# CHARGER_BOARD.net
KiCad netlist of a schematic drawn in Altium Designer
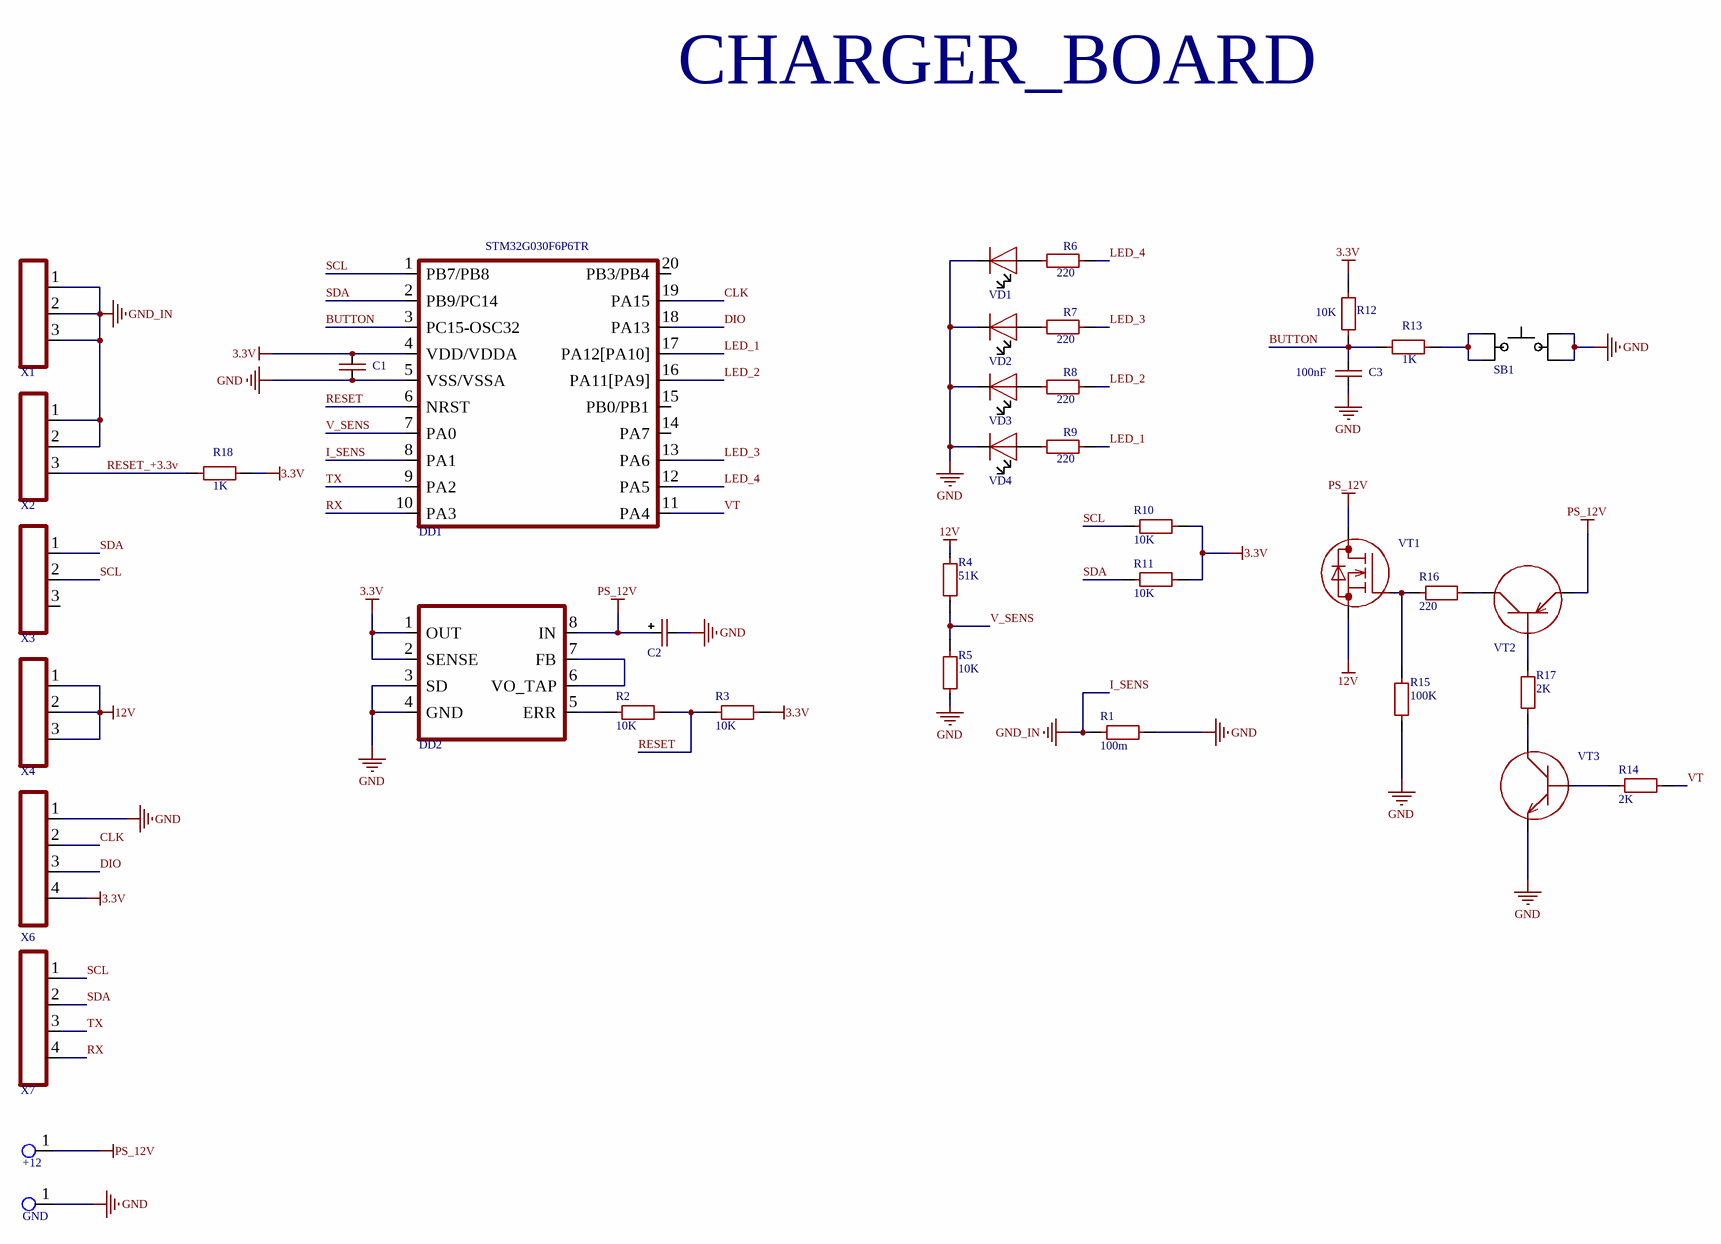
[diagram p0: CHARGER_BOARD.SchDoc]

(export (version "E")
  (design (tool "Eeschema 10.0.6"))
  (components
    (comp (ref "+12") (value "Test_Point_PCB") (footprint "Point") (libsource (lib "POINT") (part "POINT")))
    (comp (ref "C1")
      (value "CAP-NON-POLAR")
      (footprint "CAP-0603")
      (libsource (lib "PASSIVE_COMPONENTS") (part "CAP-NON-POLAR"))
    )
    (comp (ref "C2")
      (value "CAP-POLAR")
      (footprint "CAP-TAN-C")
      (libsource (lib "PASSIVE_COMPONENTS") (part "CAP-POLAR"))
    )
    (comp (ref "C3")
      (value "100nF")
      (footprint "CAP-0603")
      (libsource (lib "PASSIVE_COMPONENTS") (part "CAP-NON-POLAR"))
    )
    (comp (ref "DD1")
      (value "STM32G030F6P6TR")
      (footprint "TSSOP-20")
      (libsource (lib "STM32G030F6P6TR") (part "STM32G030F6P6TR"))
    )
    (comp (ref "DD2") (value "LP2951") (footprint "SO8-150") (libsource (lib "LP2951") (part "LP2951")))
    (comp (ref "GND") (value "Test_Point_PCB") (footprint "Point") (libsource (lib "POINT") (part "POINT")))
    (comp (ref "R1")
      (value "100m")
      (footprint "RES-2512")
      (libsource (lib "PASSIVE_COMPONENTS") (part "RES-CONST"))
    )
    (comp (ref "R2")
      (value "10K")
      (footprint "RES-0603")
      (libsource (lib "PASSIVE_COMPONENTS") (part "RES-CONST"))
    )
    (comp (ref "R3")
      (value "10K")
      (footprint "RES-0603")
      (libsource (lib "PASSIVE_COMPONENTS") (part "RES-CONST"))
    )
    (comp (ref "R4")
      (value "51K")
      (footprint "RES-0603")
      (libsource (lib "PASSIVE_COMPONENTS") (part "RES-CONST"))
    )
    (comp (ref "R5")
      (value "10K")
      (footprint "RES-0603")
      (libsource (lib "PASSIVE_COMPONENTS") (part "RES-CONST"))
    )
    (comp (ref "R6")
      (value "220")
      (footprint "RES-0603")
      (libsource (lib "PASSIVE_COMPONENTS") (part "RES-CONST"))
    )
    (comp (ref "R7")
      (value "220")
      (footprint "RES-0603")
      (libsource (lib "PASSIVE_COMPONENTS") (part "RES-CONST"))
    )
    (comp (ref "R8")
      (value "220")
      (footprint "RES-0603")
      (libsource (lib "PASSIVE_COMPONENTS") (part "RES-CONST"))
    )
    (comp (ref "R9")
      (value "220")
      (footprint "RES-0603")
      (libsource (lib "PASSIVE_COMPONENTS") (part "RES-CONST"))
    )
    (comp (ref "R10")
      (value "10K")
      (footprint "RES-0603")
      (libsource (lib "PASSIVE_COMPONENTS") (part "RES-CONST"))
    )
    (comp (ref "R11")
      (value "10K")
      (footprint "RES-0603")
      (libsource (lib "PASSIVE_COMPONENTS") (part "RES-CONST"))
    )
    (comp (ref "R12")
      (value "10K")
      (footprint "RES-0603")
      (libsource (lib "PASSIVE_COMPONENTS") (part "RES-CONST"))
    )
    (comp (ref "R13")
      (value "1K")
      (footprint "RES-0603")
      (libsource (lib "PASSIVE_COMPONENTS") (part "RES-CONST"))
    )
    (comp (ref "R14")
      (value "2K")
      (footprint "RES-0603")
      (libsource (lib "PASSIVE_COMPONENTS") (part "RES-CONST"))
    )
    (comp (ref "R15")
      (value "100K")
      (footprint "RES-0603")
      (libsource (lib "PASSIVE_COMPONENTS") (part "RES-CONST"))
    )
    (comp (ref "R16")
      (value "220")
      (footprint "RES-0603")
      (libsource (lib "PASSIVE_COMPONENTS") (part "RES-CONST"))
    )
    (comp (ref "R17")
      (value "2K")
      (footprint "RES-0603")
      (libsource (lib "PASSIVE_COMPONENTS") (part "RES-CONST"))
    )
    (comp (ref "R18")
      (value "1K")
      (footprint "RES-0603")
      (libsource (lib "PASSIVE_COMPONENTS") (part "RES-CONST"))
    )
    (comp (ref "SB1")
      (value "BUTTON-TACT-4PIN")
      (footprint "TACTB-6x6 SMD")
      (libsource (lib "TACTB-6x6 SMD") (part "BUTTON-TACT-4PIN"))
    )
    (comp (ref "VD1") (value "LED") (footprint "LED-0603") (libsource (lib "LED") (part "LED")))
    (comp (ref "VD2") (value "LED") (footprint "LED-0603") (libsource (lib "LED") (part "LED")))
    (comp (ref "VD3") (value "LED") (footprint "LED-0603") (libsource (lib "LED") (part "LED")))
    (comp (ref "VD4") (value "LED") (footprint "LED-0603") (libsource (lib "LED") (part "LED")))
    (comp (ref "VT1")
      (value "MOSFET-N-GDS")
      (footprint "TO252")
      (libsource (lib "AOD514") (part "MOSFET-N-GDS"))
    )
    (comp (ref "VT2") (value "BC857-BEC") (footprint "SOT23-3") (libsource (lib "BC8XX") (part "BC857-BEC")))
    (comp (ref "VT3") (value "BC847-BEC") (footprint "SOT23-3") (libsource (lib "BC8XX") (part "BC847-BEC")))
    (comp (ref "X1")
      (value "CONN-3-PIN")
      (footprint "4-SMD")
      (libsource (lib "Spring Compression Contact 2.5 mm") (part "CONN-3-PIN"))
    )
    (comp (ref "X2")
      (value "CONN-3-PIN")
      (footprint "4-SMD")
      (libsource (lib "Spring Compression Contact 2.5 mm") (part "CONN-3-PIN"))
    )
    (comp (ref "X3")
      (value "CONN-3-PIN")
      (footprint "4-SMD")
      (libsource (lib "Spring Compression Contact 2.5 mm") (part "CONN-3-PIN"))
    )
    (comp (ref "X4")
      (value "CONN-3-PIN")
      (footprint "4-SMD")
      (libsource (lib "Spring Compression Contact 2.5 mm") (part "CONN-3-PIN"))
    )
    (comp (ref "X6")
      (value "CONN-4-PIN")
      (footprint "CONN-PLS-4-2.54mm")
      (libsource (lib "CONNECTORS") (part "CONN-4-PIN"))
    )
    (comp (ref "X7")
      (value "CONN-4-PIN")
      (footprint "CONN-PLS-4-2.54mm")
      (libsource (lib "CONNECTORS") (part "CONN-4-PIN"))
    )
  )
  (nets
    (net (code "1") (name "/BUTTON") (class "Default")
      (node (ref "C3") (pin "2") (pinfunction "2_2") (pintype "passive"))
      (node (ref "DD1") (pin "3") (pinfunction "PC15-OSC32_3") (pintype "passive"))
      (node (ref "R12") (pin "1") (pinfunction "1_1") (pintype "passive"))
      (node (ref "R13") (pin "1") (pinfunction "1_1") (pintype "passive"))
    )
    (net (code "2") (name "/CLK") (class "Default")
      (node (ref "DD1") (pin "19") (pinfunction "PA15_19") (pintype "passive"))
      (node (ref "X6") (pin "2") (pinfunction "2_2") (pintype "passive"))
    )
    (net (code "3") (name "/DIO") (class "Default")
      (node (ref "DD1") (pin "18") (pinfunction "PA13_18") (pintype "passive"))
      (node (ref "X6") (pin "3") (pinfunction "3_3") (pintype "passive"))
    )
    (net (code "4") (name "/LED_1") (class "Default")
      (node (ref "DD1") (pin "17") (pinfunction "PA12[PA10]_17") (pintype "passive"))
      (node (ref "R9") (pin "2") (pinfunction "2_2") (pintype "passive"))
    )
    (net (code "5") (name "/LED_2") (class "Default")
      (node (ref "DD1") (pin "16") (pinfunction "PA11[PA9]_16") (pintype "passive"))
      (node (ref "R8") (pin "2") (pinfunction "2_2") (pintype "passive"))
    )
    (net (code "6") (name "/LED_3") (class "Default")
      (node (ref "DD1") (pin "13") (pinfunction "PA6_13") (pintype "passive"))
      (node (ref "R7") (pin "2") (pinfunction "2_2") (pintype "passive"))
    )
    (net (code "7") (name "/LED_4") (class "Default")
      (node (ref "DD1") (pin "12") (pinfunction "PA5_12") (pintype "passive"))
      (node (ref "R6") (pin "2") (pinfunction "2_2") (pintype "passive"))
    )
    (net (code "8") (name "/RESET") (class "Default")
      (node (ref "DD1") (pin "6") (pinfunction "NRST_6") (pintype "passive"))
      (node (ref "R2") (pin "1") (pinfunction "1_1") (pintype "passive"))
      (node (ref "R3") (pin "2") (pinfunction "2_2") (pintype "passive"))
    )
    (net (code "9") (name "/RESET_+3.3v") (class "Default")
      (node (ref "R18") (pin "1") (pinfunction "1_1") (pintype "passive"))
      (node (ref "X2") (pin "3") (pinfunction "3_3") (pintype "passive"))
    )
    (net (code "10") (name "/RX") (class "Default")
      (node (ref "DD1") (pin "10") (pinfunction "PA3_10") (pintype "passive"))
      (node (ref "X7") (pin "4") (pinfunction "4_4") (pintype "passive"))
    )
    (net (code "11") (name "/SCL") (class "Default")
      (node (ref "DD1") (pin "1") (pinfunction "PB7/PB8_1") (pintype "passive"))
      (node (ref "R10") (pin "2") (pinfunction "2_2") (pintype "passive"))
      (node (ref "X3") (pin "2") (pinfunction "2_2") (pintype "passive"))
      (node (ref "X7") (pin "1") (pinfunction "1_1") (pintype "passive"))
    )
    (net (code "12") (name "/SDA") (class "Default")
      (node (ref "DD1") (pin "2") (pinfunction "PB9/PC14_2") (pintype "passive"))
      (node (ref "R11") (pin "2") (pinfunction "2_2") (pintype "passive"))
      (node (ref "X3") (pin "1") (pinfunction "1_1") (pintype "passive"))
      (node (ref "X7") (pin "2") (pinfunction "2_2") (pintype "passive"))
    )
    (net (code "13") (name "/TX") (class "Default")
      (node (ref "DD1") (pin "9") (pinfunction "PA2_9") (pintype "passive"))
      (node (ref "X7") (pin "3") (pinfunction "3_3") (pintype "passive"))
    )
    (net (code "14") (name "/VT") (class "Default")
      (node (ref "DD1") (pin "11") (pinfunction "PA4_11") (pintype "passive"))
      (node (ref "R14") (pin "1") (pinfunction "1_1") (pintype "passive"))
    )
    (net (code "15") (name "/V_SENS") (class "Default")
      (node (ref "DD1") (pin "7") (pinfunction "PA0_7") (pintype "passive"))
      (node (ref "R4") (pin "2") (pinfunction "2_2") (pintype "passive"))
      (node (ref "R5") (pin "1") (pinfunction "1_1") (pintype "passive"))
    )
    (net (code "16") (name "3.3V") (class "Default")
      (node (ref "C1") (pin "2") (pinfunction "2_2") (pintype "passive"))
      (node (ref "DD1") (pin "4") (pinfunction "VDD/VDDA_4") (pintype "passive"))
      (node (ref "DD2") (pin "1") (pinfunction "OUT_1") (pintype "passive"))
      (node (ref "DD2") (pin "2") (pinfunction "SENSE_2") (pintype "passive"))
      (node (ref "R10") (pin "1") (pinfunction "1_1") (pintype "passive"))
      (node (ref "R11") (pin "1") (pinfunction "1_1") (pintype "passive"))
      (node (ref "R12") (pin "2") (pinfunction "2_2") (pintype "passive"))
      (node (ref "R18") (pin "2") (pinfunction "2_2") (pintype "passive"))
      (node (ref "R3") (pin "1") (pinfunction "1_1") (pintype "passive"))
      (node (ref "X6") (pin "4") (pinfunction "4_4") (pintype "passive"))
    )
    (net (code "17") (name "12V") (class "Default")
      (node (ref "R4") (pin "1") (pinfunction "1_1") (pintype "passive"))
      (node (ref "VT1") (pin "3") (pinfunction "S_3") (pintype "passive"))
      (node (ref "X4") (pin "1") (pinfunction "1_1") (pintype "passive"))
      (node (ref "X4") (pin "2") (pinfunction "2_2") (pintype "passive"))
      (node (ref "X4") (pin "3") (pinfunction "3_3") (pintype "passive"))
    )
    (net (code "18") (name "GND") (class "Default")
      (node (ref "C1") (pin "1") (pinfunction "1_1") (pintype "passive"))
      (node (ref "C2") (pin "2") (pinfunction "-_2") (pintype "passive"))
      (node (ref "C3") (pin "1") (pinfunction "1_1") (pintype "passive"))
      (node (ref "DD1") (pin "5") (pinfunction "VSS/VSSA_5") (pintype "passive"))
      (node (ref "DD2") (pin "3") (pinfunction "SD_3") (pintype "passive"))
      (node (ref "DD2") (pin "4") (pinfunction "GND_4") (pintype "passive"))
      (node (ref "GND") (pin "1") (pinfunction "G9_1") (pintype "passive"))
      (node (ref "R1") (pin "2") (pinfunction "2_2") (pintype "passive"))
      (node (ref "R15") (pin "1") (pinfunction "1_1") (pintype "passive"))
      (node (ref "R5") (pin "2") (pinfunction "2_2") (pintype "passive"))
      (node (ref "SB1") (pin "3") (pintype "passive"))
      (node (ref "SB1") (pin "4") (pintype "passive"))
      (node (ref "VD1") (pin "1") (pinfunction "C_1") (pintype "passive"))
      (node (ref "VD2") (pin "1") (pinfunction "C_1") (pintype "passive"))
      (node (ref "VD3") (pin "1") (pinfunction "C_1") (pintype "passive"))
      (node (ref "VD4") (pin "1") (pinfunction "C_1") (pintype "passive"))
      (node (ref "VT3") (pin "2") (pinfunction "E_2") (pintype "passive"))
      (node (ref "X6") (pin "1") (pinfunction "1_1") (pintype "passive"))
    )
    (net (code "19") (name "GND_IN") (class "Default")
      (node (ref "DD1") (pin "8") (pinfunction "PA1_8") (pintype "passive"))
      (node (ref "R1") (pin "1") (pinfunction "1_1") (pintype "passive"))
      (node (ref "X1") (pin "1") (pinfunction "1_1") (pintype "passive"))
      (node (ref "X1") (pin "2") (pinfunction "2_2") (pintype "passive"))
      (node (ref "X1") (pin "3") (pinfunction "3_3") (pintype "passive"))
      (node (ref "X2") (pin "1") (pinfunction "1_1") (pintype "passive"))
      (node (ref "X2") (pin "2") (pinfunction "2_2") (pintype "passive"))
    )
    (net (code "20") (name "Net-(DD2-ERR)") (class "Default")
      (node (ref "DD2") (pin "5") (pinfunction "ERR_5") (pintype "passive"))
      (node (ref "R2") (pin "2") (pinfunction "2_2") (pintype "passive"))
    )
    (net (code "21") (name "Net-(DD2-FB)") (class "Default")
      (node (ref "DD2") (pin "6") (pinfunction "VO_TAP_6") (pintype "passive"))
      (node (ref "DD2") (pin "7") (pinfunction "FB_7") (pintype "passive"))
    )
    (net (code "22") (name "Net-(R13-Pad2)") (class "Default")
      (node (ref "R13") (pin "2") (pinfunction "2_2") (pintype "passive"))
      (node (ref "SB1") (pin "1") (pintype "passive"))
      (node (ref "SB1") (pin "2") (pintype "passive"))
    )
    (net (code "23") (name "Net-(VD1-A)") (class "Default")
      (node (ref "R6") (pin "1") (pinfunction "1_1") (pintype "passive"))
      (node (ref "VD1") (pin "2") (pinfunction "A_2") (pintype "passive"))
    )
    (net (code "24") (name "Net-(VD2-A)") (class "Default")
      (node (ref "R7") (pin "1") (pinfunction "1_1") (pintype "passive"))
      (node (ref "VD2") (pin "2") (pinfunction "A_2") (pintype "passive"))
    )
    (net (code "25") (name "Net-(VD3-A)") (class "Default")
      (node (ref "R8") (pin "1") (pinfunction "1_1") (pintype "passive"))
      (node (ref "VD3") (pin "2") (pinfunction "A_2") (pintype "passive"))
    )
    (net (code "26") (name "Net-(VD4-A)") (class "Default")
      (node (ref "R9") (pin "1") (pinfunction "1_1") (pintype "passive"))
      (node (ref "VD4") (pin "2") (pinfunction "A_2") (pintype "passive"))
    )
    (net (code "27") (name "Net-(VT1-G)") (class "Default")
      (node (ref "R15") (pin "2") (pinfunction "2_2") (pintype "passive"))
      (node (ref "R16") (pin "1") (pinfunction "1_1") (pintype "passive"))
      (node (ref "VT1") (pin "1") (pinfunction "G_1") (pintype "passive"))
    )
    (net (code "28") (name "Net-(VT2-B)") (class "Default")
      (node (ref "R17") (pin "1") (pinfunction "1_1") (pintype "passive"))
      (node (ref "VT2") (pin "1") (pinfunction "B_1") (pintype "passive"))
    )
    (net (code "29") (name "Net-(VT2-C)") (class "Default")
      (node (ref "R16") (pin "2") (pinfunction "2_2") (pintype "passive"))
      (node (ref "VT2") (pin "3") (pinfunction "C_3") (pintype "passive"))
    )
    (net (code "30") (name "Net-(VT3-B)") (class "Default")
      (node (ref "R14") (pin "2") (pinfunction "2_2") (pintype "passive"))
      (node (ref "VT3") (pin "1") (pinfunction "B_1") (pintype "passive"))
    )
    (net (code "31") (name "Net-(VT3-C)") (class "Default")
      (node (ref "R17") (pin "2") (pinfunction "2_2") (pintype "passive"))
      (node (ref "VT3") (pin "3") (pinfunction "C_3") (pintype "passive"))
    )
    (net (code "32") (name "PS_12V") (class "Default")
      (node (ref "+12") (pin "1") (pinfunction "G9_1") (pintype "passive"))
      (node (ref "C2") (pin "1") (pinfunction "+_1") (pintype "passive"))
      (node (ref "DD2") (pin "8") (pinfunction "IN_8") (pintype "passive"))
      (node (ref "VT1") (pin "2") (pinfunction "D_2") (pintype "passive"))
      (node (ref "VT2") (pin "2") (pinfunction "E_2") (pintype "passive"))
    )
    (net (code "33") (name "unconnected-(DD1-PA7-Pad14)") (class "Default")
      (node (ref "DD1") (pin "14") (pinfunction "PA7_14") (pintype "passive"))
    )
    (net (code "34") (name "unconnected-(DD1-PB0{slash}PB1-Pad15)") (class "Default")
      (node (ref "DD1") (pin "15") (pinfunction "PB0/PB1_15") (pintype "passive"))
    )
    (net (code "35") (name "unconnected-(DD1-PB3{slash}PB4-Pad20)") (class "Default")
      (node (ref "DD1") (pin "20") (pinfunction "PB3/PB4_20") (pintype "passive"))
    )
    (net (code "36") (name "unconnected-(X3-Pad3)") (class "Default")
      (node (ref "X3") (pin "3") (pinfunction "3_3") (pintype "passive"))
    )
  )
)
